# RobotArm.net
KiCad netlist of a schematic drawn in EAGLE
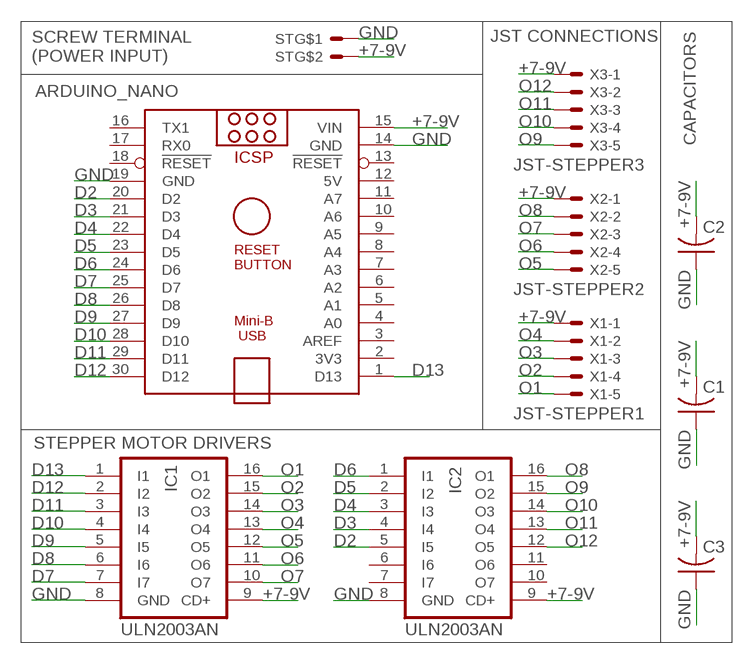
[diagram p0: schematic, sheet 1]

(export (version "E")
  (design (tool "Eeschema 10.0.6"))
  (components
    (comp (ref "ARDUINO_NANO")
      (value "ARDUINO_NANO")
      (footprint "eagle-import:ARDUINO_NANO")
      (libsource (lib "eagle-import") (part "ARDUINO_NANO"))
    )
    (comp (ref "C1")
      (value "C-US050-024X044")
      (footprint "eagle-import:C050-024X044")
      (libsource (lib "eagle-import") (part "C-US050-024X044"))
    )
    (comp (ref "C2")
      (value "C-US050-024X044")
      (footprint "eagle-import:C050-024X044")
      (libsource (lib "eagle-import") (part "C-US050-024X044"))
    )
    (comp (ref "C3")
      (value "C-US050-024X044")
      (footprint "eagle-import:C050-024X044")
      (libsource (lib "eagle-import") (part "C-US050-024X044"))
    )
    (comp (ref "IC1")
      (value "ULN2003AN")
      (footprint "eagle-import:DIL16")
      (libsource (lib "eagle-import") (part "ULN2003AN"))
    )
    (comp (ref "IC2")
      (value "ULN2003AN")
      (footprint "eagle-import:DIL16")
      (libsource (lib "eagle-import") (part "ULN2003AN"))
    )
    (comp (ref "ST")
      (value "SCREWTERMINAL2.54")
      (footprint "eagle-import:2.54MM")
      (libsource (lib "eagle-import") (part "SCREWTERMINAL2.54"))
    )
    (comp (ref "X1")
      (value "JST-STEPPER1")
      (footprint "eagle-import:JST-XH-05-PACKAGE-LONG-PAD")
      (libsource (lib "eagle-import") (part "JST-XH-05-PIN-LONG-PAD"))
    )
    (comp (ref "X2")
      (value "JST-STEPPER2")
      (footprint "eagle-import:JST-XH-05-PACKAGE-LONG-PAD")
      (libsource (lib "eagle-import") (part "JST-XH-05-PIN-LONG-PAD"))
    )
    (comp (ref "X3")
      (value "JST-STEPPER3")
      (footprint "eagle-import:JST-XH-05-PACKAGE-LONG-PAD")
      (libsource (lib "eagle-import") (part "JST-XH-05-PIN-LONG-PAD"))
    )
  )
  (nets
    (net (code "1") (name "/+7-9V") (class "Default")
      (node (ref "ARDUINO_NANO") (pin "15") (pinfunction "VIN_15") (pintype "power_in"))
      (node (ref "C1") (pin "2") (pinfunction "2_2") (pintype "passive"))
      (node (ref "C2") (pin "2") (pinfunction "2_2") (pintype "passive"))
      (node (ref "C3") (pin "2") (pinfunction "2_2") (pintype "passive"))
      (node (ref "IC1") (pin "9") (pinfunction "CD+_9") (pintype "passive"))
      (node (ref "IC2") (pin "9") (pinfunction "CD+_9") (pintype "passive"))
      (node (ref "ST") (pin "P$2") (pinfunction "S_P$2") (pintype "passive"))
      (node (ref "X1") (pin "1") (pinfunction "S_1") (pintype "passive"))
      (node (ref "X2") (pin "1") (pinfunction "S_1") (pintype "passive"))
      (node (ref "X3") (pin "1") (pinfunction "S_1") (pintype "passive"))
    )
    (net (code "2") (name "/5V") (class "Default")
      (node (ref "ARDUINO_NANO") (pin "12") (pinfunction "5V_12") (pintype "power_in"))
    )
    (net (code "3") (name "/D2") (class "Default")
      (node (ref "ARDUINO_NANO") (pin "20") (pinfunction "D2_20") (pintype "bidirectional"))
      (node (ref "IC2") (pin "5") (pinfunction "I5_5") (pintype "input"))
    )
    (net (code "4") (name "/D3") (class "Default")
      (node (ref "ARDUINO_NANO") (pin "21") (pinfunction "D3_21") (pintype "bidirectional"))
      (node (ref "IC2") (pin "4") (pinfunction "I4_4") (pintype "input"))
    )
    (net (code "5") (name "/D4") (class "Default")
      (node (ref "ARDUINO_NANO") (pin "22") (pinfunction "D4_22") (pintype "bidirectional"))
      (node (ref "IC2") (pin "3") (pinfunction "I3_3") (pintype "input"))
    )
    (net (code "6") (name "/D5") (class "Default")
      (node (ref "ARDUINO_NANO") (pin "23") (pinfunction "D5_23") (pintype "bidirectional"))
      (node (ref "IC2") (pin "2") (pinfunction "I2_2") (pintype "input"))
    )
    (net (code "7") (name "/D6") (class "Default")
      (node (ref "ARDUINO_NANO") (pin "24") (pinfunction "D6_24") (pintype "bidirectional"))
      (node (ref "IC2") (pin "1") (pinfunction "I1_1") (pintype "input"))
    )
    (net (code "8") (name "/D7") (class "Default")
      (node (ref "ARDUINO_NANO") (pin "25") (pinfunction "D7_25") (pintype "bidirectional"))
      (node (ref "IC1") (pin "7") (pinfunction "I7_7") (pintype "input"))
    )
    (net (code "9") (name "/D8") (class "Default")
      (node (ref "ARDUINO_NANO") (pin "26") (pinfunction "D8_26") (pintype "bidirectional"))
      (node (ref "IC1") (pin "6") (pinfunction "I6_6") (pintype "input"))
    )
    (net (code "10") (name "/D9") (class "Default")
      (node (ref "ARDUINO_NANO") (pin "27") (pinfunction "D9_27") (pintype "bidirectional"))
      (node (ref "IC1") (pin "5") (pinfunction "I5_5") (pintype "input"))
    )
    (net (code "11") (name "/D10") (class "Default")
      (node (ref "ARDUINO_NANO") (pin "28") (pinfunction "D10_28") (pintype "bidirectional"))
      (node (ref "IC1") (pin "4") (pinfunction "I4_4") (pintype "input"))
    )
    (net (code "12") (name "/D11") (class "Default")
      (node (ref "ARDUINO_NANO") (pin "29") (pinfunction "D11_29") (pintype "bidirectional"))
      (node (ref "IC1") (pin "3") (pinfunction "I3_3") (pintype "input"))
    )
    (net (code "13") (name "/D12") (class "Default")
      (node (ref "ARDUINO_NANO") (pin "30") (pinfunction "D12_30") (pintype "bidirectional"))
      (node (ref "IC1") (pin "2") (pinfunction "I2_2") (pintype "input"))
    )
    (net (code "14") (name "/D13") (class "Default")
      (node (ref "ARDUINO_NANO") (pin "1") (pinfunction "D13_1") (pintype "bidirectional"))
      (node (ref "IC1") (pin "1") (pinfunction "I1_1") (pintype "input"))
    )
    (net (code "15") (name "/GND") (class "Default")
      (node (ref "ARDUINO_NANO") (pin "14") (pinfunction "GND_14") (pintype "power_in"))
      (node (ref "ARDUINO_NANO") (pin "19") (pinfunction "GND_19") (pintype "power_in"))
      (node (ref "C1") (pin "1") (pinfunction "1_1") (pintype "passive"))
      (node (ref "C2") (pin "1") (pinfunction "1_1") (pintype "passive"))
      (node (ref "C3") (pin "1") (pinfunction "1_1") (pintype "passive"))
      (node (ref "IC1") (pin "8") (pinfunction "GND_8") (pintype "power_in"))
      (node (ref "IC2") (pin "8") (pinfunction "GND_8") (pintype "power_in"))
      (node (ref "ST") (pin "P$1") (pinfunction "S_P$1") (pintype "passive"))
    )
    (net (code "16") (name "/O1") (class "Default")
      (node (ref "IC1") (pin "16") (pinfunction "O1_16") (pintype "open_collector"))
      (node (ref "X1") (pin "5") (pinfunction "S_5") (pintype "passive"))
    )
    (net (code "17") (name "/O2") (class "Default")
      (node (ref "IC1") (pin "15") (pinfunction "O2_15") (pintype "open_collector"))
      (node (ref "X1") (pin "4") (pinfunction "S_4") (pintype "passive"))
    )
    (net (code "18") (name "/O3") (class "Default")
      (node (ref "IC1") (pin "14") (pinfunction "O3_14") (pintype "open_collector"))
      (node (ref "X1") (pin "3") (pinfunction "S_3") (pintype "passive"))
    )
    (net (code "19") (name "/O4") (class "Default")
      (node (ref "IC1") (pin "13") (pinfunction "O4_13") (pintype "open_collector"))
      (node (ref "X1") (pin "2") (pinfunction "S_2") (pintype "passive"))
    )
    (net (code "20") (name "/O5") (class "Default")
      (node (ref "IC1") (pin "12") (pinfunction "O5_12") (pintype "open_collector"))
      (node (ref "X2") (pin "5") (pinfunction "S_5") (pintype "passive"))
    )
    (net (code "21") (name "/O6") (class "Default")
      (node (ref "IC1") (pin "11") (pinfunction "O6_11") (pintype "open_collector"))
      (node (ref "X2") (pin "4") (pinfunction "S_4") (pintype "passive"))
    )
    (net (code "22") (name "/O7") (class "Default")
      (node (ref "IC1") (pin "10") (pinfunction "O7_10") (pintype "open_collector"))
      (node (ref "X2") (pin "3") (pinfunction "S_3") (pintype "passive"))
    )
    (net (code "23") (name "/O8") (class "Default")
      (node (ref "IC2") (pin "16") (pinfunction "O1_16") (pintype "open_collector"))
      (node (ref "X2") (pin "2") (pinfunction "S_2") (pintype "passive"))
    )
    (net (code "24") (name "/O9") (class "Default")
      (node (ref "IC2") (pin "15") (pinfunction "O2_15") (pintype "open_collector"))
      (node (ref "X3") (pin "5") (pinfunction "S_5") (pintype "passive"))
    )
    (net (code "25") (name "/O10") (class "Default")
      (node (ref "IC2") (pin "14") (pinfunction "O3_14") (pintype "open_collector"))
      (node (ref "X3") (pin "4") (pinfunction "S_4") (pintype "passive"))
    )
    (net (code "26") (name "/O11") (class "Default")
      (node (ref "IC2") (pin "13") (pinfunction "O4_13") (pintype "open_collector"))
      (node (ref "X3") (pin "3") (pinfunction "S_3") (pintype "passive"))
    )
    (net (code "27") (name "/O12") (class "Default")
      (node (ref "IC2") (pin "12") (pinfunction "O5_12") (pintype "open_collector"))
      (node (ref "X3") (pin "2") (pinfunction "S_2") (pintype "passive"))
    )
    (net (code "28") (name "unconnected-(ARDUINO_NANO-3V3-Pad2)") (class "Default")
      (node (ref "ARDUINO_NANO") (pin "2") (pinfunction "3V3_2") (pintype "output"))
    )
    (net (code "29") (name "unconnected-(ARDUINO_NANO-A0-Pad4)") (class "Default")
      (node (ref "ARDUINO_NANO") (pin "4") (pinfunction "A0_4") (pintype "bidirectional"))
    )
    (net (code "30") (name "unconnected-(ARDUINO_NANO-A1-Pad5)") (class "Default")
      (node (ref "ARDUINO_NANO") (pin "5") (pinfunction "A1_5") (pintype "bidirectional"))
    )
    (net (code "31") (name "unconnected-(ARDUINO_NANO-A2-Pad6)") (class "Default")
      (node (ref "ARDUINO_NANO") (pin "6") (pinfunction "A2_6") (pintype "bidirectional"))
    )
    (net (code "32") (name "unconnected-(ARDUINO_NANO-A3-Pad7)") (class "Default")
      (node (ref "ARDUINO_NANO") (pin "7") (pinfunction "A3_7") (pintype "bidirectional"))
    )
    (net (code "33") (name "unconnected-(ARDUINO_NANO-A4-Pad8)") (class "Default")
      (node (ref "ARDUINO_NANO") (pin "8") (pinfunction "A4_8") (pintype "bidirectional"))
    )
    (net (code "34") (name "unconnected-(ARDUINO_NANO-A5-Pad9)") (class "Default")
      (node (ref "ARDUINO_NANO") (pin "9") (pinfunction "A5_9") (pintype "bidirectional"))
    )
    (net (code "35") (name "unconnected-(ARDUINO_NANO-A6-Pad10)") (class "Default")
      (node (ref "ARDUINO_NANO") (pin "10") (pinfunction "A6_10") (pintype "bidirectional"))
    )
    (net (code "36") (name "unconnected-(ARDUINO_NANO-A7-Pad11)") (class "Default")
      (node (ref "ARDUINO_NANO") (pin "11") (pinfunction "A7_11") (pintype "bidirectional"))
    )
    (net (code "37") (name "unconnected-(ARDUINO_NANO-AREF-Pad3)") (class "Default")
      (node (ref "ARDUINO_NANO") (pin "3") (pinfunction "AREF_3") (pintype "input"))
    )
    (net (code "38") (name "unconnected-(ARDUINO_NANO-RX0-Pad17)") (class "Default")
      (node (ref "ARDUINO_NANO") (pin "17") (pinfunction "RX0_17") (pintype "bidirectional"))
    )
    (net (code "39") (name "unconnected-(ARDUINO_NANO-TX1-Pad16)") (class "Default")
      (node (ref "ARDUINO_NANO") (pin "16") (pinfunction "TX1_16") (pintype "bidirectional"))
    )
    (net (code "40") (name "unconnected-(ARDUINO_NANO-~{RESET}-Pad13)") (class "Default")
      (node (ref "ARDUINO_NANO") (pin "13") (pinfunction "~{RESET}_13") (pintype "input"))
    )
    (net (code "41") (name "unconnected-(ARDUINO_NANO-~{RESET}-Pad18)") (class "Default")
      (node (ref "ARDUINO_NANO") (pin "18") (pinfunction "~{RESET}_18") (pintype "input"))
    )
    (net (code "42") (name "unconnected-(IC2-I6-Pad6)") (class "Default")
      (node (ref "IC2") (pin "6") (pinfunction "I6_6") (pintype "input"))
    )
    (net (code "43") (name "unconnected-(IC2-I7-Pad7)") (class "Default")
      (node (ref "IC2") (pin "7") (pinfunction "I7_7") (pintype "input"))
    )
    (net (code "44") (name "unconnected-(IC2-O6-Pad11)") (class "Default")
      (node (ref "IC2") (pin "11") (pinfunction "O6_11") (pintype "open_collector"))
    )
    (net (code "45") (name "unconnected-(IC2-O7-Pad10)") (class "Default")
      (node (ref "IC2") (pin "10") (pinfunction "O7_10") (pintype "open_collector"))
    )
  )
)
